# W070djg.net
KiCad netlist of a schematic drawn in EAGLE
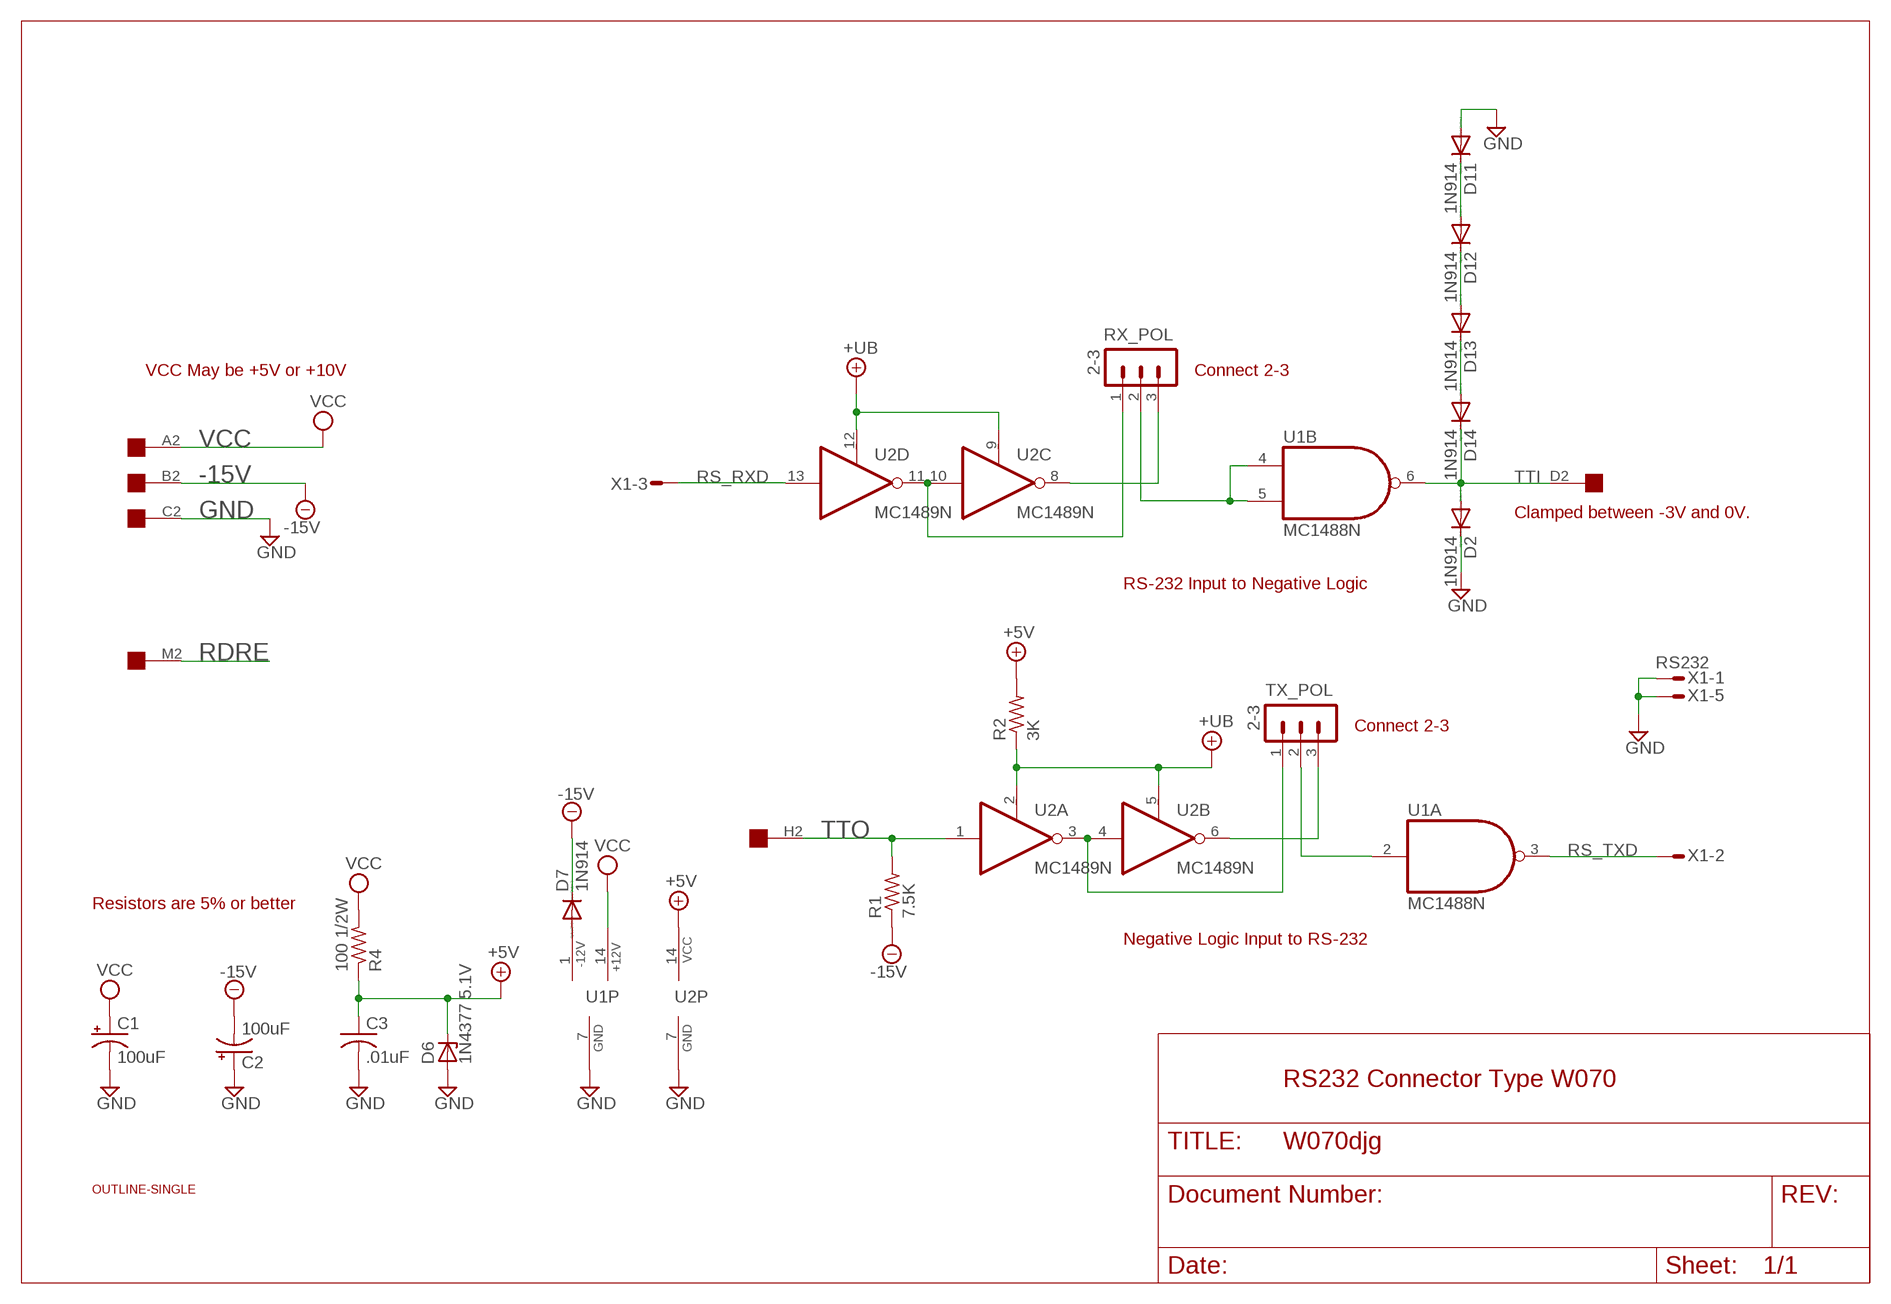
[diagram p0: schematic, sheet 1]

(export (version "E")
  (design (tool "Eeschema 10.0.6"))
  (components
    (comp (ref "C1")
      (value "100uF")
      (footprint "eagle-import:E22-9")
      (libsource (lib "eagle-import") (part "CPOL-USE22-9AXIAL"))
    )
    (comp (ref "C2")
      (value "100uF")
      (footprint "eagle-import:E22-9")
      (libsource (lib "eagle-import") (part "CPOL-USE22-9AXIAL"))
    )
    (comp (ref "C3")
      (value ".01uF")
      (footprint "eagle-import:C050-025X075")
      (libsource (lib "eagle-import") (part "C-US050-025X075"))
    )
    (comp (ref "D2")
      (value "1N914")
      (footprint "eagle-import:DO35-10")
      (libsource (lib "eagle-import") (part "1N4148DO35-10"))
    )
    (comp (ref "D6")
      (value "1N4377 5.1V")
      (footprint "eagle-import:DO35Z10")
      (libsource (lib "eagle-import") (part "ZENER-DIODEDO35Z10"))
    )
    (comp (ref "D7")
      (value "1N914")
      (footprint "eagle-import:DO35-10")
      (libsource (lib "eagle-import") (part "1N4148DO35-10"))
    )
    (comp (ref "D11")
      (value "1N914")
      (footprint "eagle-import:DO35-10")
      (libsource (lib "eagle-import") (part "1N4148DO35-10"))
    )
    (comp (ref "D12")
      (value "1N914")
      (footprint "eagle-import:DO35-10")
      (libsource (lib "eagle-import") (part "1N4148DO35-10"))
    )
    (comp (ref "D13")
      (value "1N914")
      (footprint "eagle-import:DO35-10")
      (libsource (lib "eagle-import") (part "1N4148DO35-10"))
    )
    (comp (ref "D14")
      (value "1N914")
      (footprint "eagle-import:DO35-10")
      (libsource (lib "eagle-import") (part "1N4148DO35-10"))
    )
    (comp (ref "EDGE")
      (value "EDGE-1")
      (footprint "eagle-import:EDGE-CON1")
      (libsource (lib "eagle-import") (part "EDGE-1"))
    )
    (comp (ref "R1")
      (value "7.5K")
      (footprint "eagle-import:0207_10")
      (libsource (lib "eagle-import") (part "R-US_0207/10"))
    )
    (comp (ref "R2")
      (value "3K")
      (footprint "eagle-import:0207_10")
      (libsource (lib "eagle-import") (part "R-US_0207/10"))
    )
    (comp (ref "R4")
      (value "100 1/2W")
      (footprint "eagle-import:0309_12")
      (libsource (lib "eagle-import") (part "R-US_0309/12"))
    )
    (comp (ref "RX_POL")
      (value "2-3")
      (footprint "eagle-import:MA03-1")
      (libsource (lib "eagle-import") (part "MA03-1"))
    )
    (comp (ref "TX_POL")
      (value "2-3")
      (footprint "eagle-import:MA03-1")
      (libsource (lib "eagle-import") (part "MA03-1"))
    )
    (comp (ref "U$1")
      (value "OUTLINE-SINGLE")
      (footprint "eagle-import:SINGLE")
      (libsource (lib "eagle-import") (part "OUTLINE-SINGLE"))
    )
    (comp (ref "U1")
      (value "MC1488N")
      (footprint "eagle-import:DIL14")
      (libsource (lib "eagle-import") (part "1488N"))
    )
    (comp (ref "U2")
      (value "MC1489N")
      (footprint "eagle-import:DIL14")
      (libsource (lib "eagle-import") (part "1489N"))
    )
    (comp (ref "X1")
      (value "RS232")
      (footprint "eagle-import:182-009-MALE")
      (libsource (lib "eagle-import") (part "M09?S-182"))
    )
  )
  (nets
    (net (code "1") (name "+5V") (class "Default")
      (node (ref "C3") (pin "1") (pinfunction "1_1") (pintype "passive"))
      (node (ref "D6") (pin "C") (pinfunction "C_C") (pintype "passive"))
      (node (ref "R2") (pin "2") (pinfunction "2_2") (pintype "passive"))
      (node (ref "R4") (pin "1") (pinfunction "1_1") (pintype "passive"))
      (node (ref "U2") (pin "14") (pinfunction "VCC_14") (pintype "power_in"))
    )
    (net (code "2") (name "+UB") (class "Default")
      (node (ref "R2") (pin "1") (pinfunction "1_1") (pintype "passive"))
      (node (ref "U2") (pin "12") (pinfunction "RC_12") (pintype "input"))
      (node (ref "U2") (pin "2") (pinfunction "RC_2") (pintype "input"))
      (node (ref "U2") (pin "5") (pinfunction "RC_5") (pintype "input"))
      (node (ref "U2") (pin "9") (pinfunction "RC_9") (pintype "input"))
    )
    (net (code "3") (name "-15V") (class "Default")
      (node (ref "C2") (pin "-") (pinfunction "-_-") (pintype "passive"))
      (node (ref "D7") (pin "C") (pinfunction "C_C") (pintype "passive"))
      (node (ref "EDGE") (pin "B2") (pinfunction "1_B2") (pintype "bidirectional"))
      (node (ref "R1") (pin "1") (pinfunction "1_1") (pintype "passive"))
    )
    (net (code "4") (name "/RDRE") (class "Default")
      (node (ref "EDGE") (pin "M2") (pinfunction "1_M2") (pintype "bidirectional"))
    )
    (net (code "5") (name "/RS_RXD") (class "Default")
      (node (ref "U2") (pin "13") (pinfunction "I_13") (pintype "input"))
      (node (ref "X1") (pin "3") (pinfunction "M_3") (pintype "passive"))
    )
    (net (code "6") (name "/RS_TXD") (class "Default")
      (node (ref "U1") (pin "3") (pinfunction "O_3") (pintype "output"))
      (node (ref "X1") (pin "2") (pinfunction "M_2") (pintype "passive"))
    )
    (net (code "7") (name "/TTI") (class "Default")
      (node (ref "D14") (pin "C") (pinfunction "C_C") (pintype "passive"))
      (node (ref "D2") (pin "A") (pinfunction "A_A") (pintype "passive"))
      (node (ref "EDGE") (pin "D2") (pinfunction "1_D2") (pintype "bidirectional"))
      (node (ref "U1") (pin "6") (pinfunction "O_6") (pintype "output"))
    )
    (net (code "8") (name "/TTO") (class "Default")
      (node (ref "EDGE") (pin "H2") (pinfunction "1_H2") (pintype "bidirectional"))
      (node (ref "R1") (pin "2") (pinfunction "2_2") (pintype "passive"))
      (node (ref "U2") (pin "1") (pinfunction "I_1") (pintype "input"))
    )
    (net (code "9") (name "GND") (class "Default")
      (node (ref "C1") (pin "-") (pinfunction "-_-") (pintype "passive"))
      (node (ref "C2") (pin "+") (pinfunction "+_+") (pintype "passive"))
      (node (ref "C3") (pin "2") (pinfunction "2_2") (pintype "passive"))
      (node (ref "D11") (pin "A") (pinfunction "A_A") (pintype "passive"))
      (node (ref "D2") (pin "C") (pinfunction "C_C") (pintype "passive"))
      (node (ref "D6") (pin "A") (pinfunction "A_A") (pintype "passive"))
      (node (ref "EDGE") (pin "C2") (pinfunction "1_C2") (pintype "bidirectional"))
      (node (ref "U1") (pin "7") (pinfunction "GND_7") (pintype "power_in"))
      (node (ref "U2") (pin "7") (pinfunction "GND_7") (pintype "power_in"))
      (node (ref "X1") (pin "1") (pinfunction "M_1") (pintype "passive"))
      (node (ref "X1") (pin "5") (pinfunction "M_5") (pintype "passive"))
    )
    (net (code "10") (name "Net-(D11-PadC)") (class "Default")
      (node (ref "D11") (pin "C") (pinfunction "C_C") (pintype "passive"))
      (node (ref "D12") (pin "A") (pinfunction "A_A") (pintype "passive"))
    )
    (net (code "11") (name "Net-(D12-PadC)") (class "Default")
      (node (ref "D12") (pin "C") (pinfunction "C_C") (pintype "passive"))
      (node (ref "D13") (pin "A") (pinfunction "A_A") (pintype "passive"))
    )
    (net (code "12") (name "Net-(D13-PadC)") (class "Default")
      (node (ref "D13") (pin "C") (pinfunction "C_C") (pintype "passive"))
      (node (ref "D14") (pin "A") (pinfunction "A_A") (pintype "passive"))
    )
    (net (code "13") (name "Net-(U1A-I)") (class "Default")
      (node (ref "TX_POL") (pin "2") (pinfunction "2_2") (pintype "passive"))
      (node (ref "U1") (pin "2") (pinfunction "I_2") (pintype "input"))
    )
    (net (code "14") (name "Net-(U1B-I0)") (class "Default")
      (node (ref "RX_POL") (pin "2") (pinfunction "2_2") (pintype "passive"))
      (node (ref "U1") (pin "4") (pinfunction "I0_4") (pintype "input"))
      (node (ref "U1") (pin "5") (pinfunction "I1_5") (pintype "input"))
    )
    (net (code "15") (name "Net-(U1E--12V)") (class "Default")
      (node (ref "D7") (pin "A") (pinfunction "A_A") (pintype "passive"))
      (node (ref "U1") (pin "1") (pinfunction "-12V_1") (pintype "power_in"))
    )
    (net (code "16") (name "Net-(U2A-O)") (class "Default")
      (node (ref "TX_POL") (pin "1") (pinfunction "1_1") (pintype "passive"))
      (node (ref "U2") (pin "3") (pinfunction "O_3") (pintype "output"))
      (node (ref "U2") (pin "4") (pinfunction "I_4") (pintype "input"))
    )
    (net (code "17") (name "Net-(U2B-O)") (class "Default")
      (node (ref "TX_POL") (pin "3") (pinfunction "3_3") (pintype "passive"))
      (node (ref "U2") (pin "6") (pinfunction "O_6") (pintype "output"))
    )
    (net (code "18") (name "Net-(U2C-I)") (class "Default")
      (node (ref "RX_POL") (pin "1") (pinfunction "1_1") (pintype "passive"))
      (node (ref "U2") (pin "10") (pinfunction "I_10") (pintype "input"))
      (node (ref "U2") (pin "11") (pinfunction "O_11") (pintype "output"))
    )
    (net (code "19") (name "Net-(U2C-O)") (class "Default")
      (node (ref "RX_POL") (pin "3") (pinfunction "3_3") (pintype "passive"))
      (node (ref "U2") (pin "8") (pinfunction "O_8") (pintype "output"))
    )
    (net (code "20") (name "VCC") (class "Default")
      (node (ref "C1") (pin "+") (pinfunction "+_+") (pintype "passive"))
      (node (ref "EDGE") (pin "A2") (pinfunction "1_A2") (pintype "bidirectional"))
      (node (ref "R4") (pin "2") (pinfunction "2_2") (pintype "passive"))
      (node (ref "U1") (pin "14") (pinfunction "+12V_14") (pintype "power_in"))
    )
  )
)
